# TC2030-NL_TagConnect_6-pin.net
KiCad netlist of a schematic drawn in Altium Designer
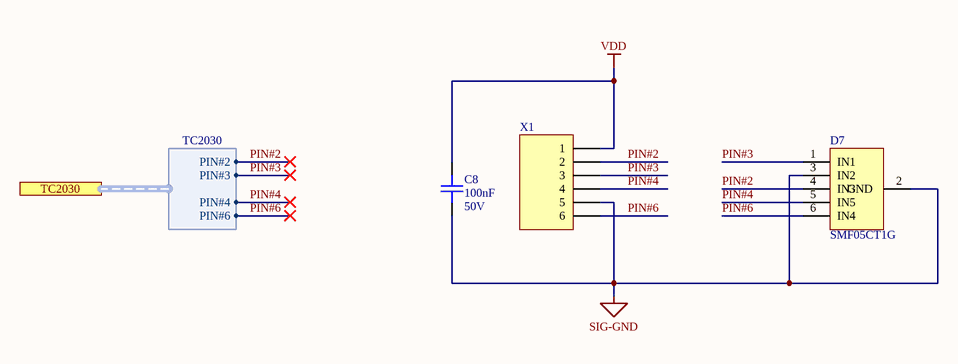
[diagram p0: TC2030-NL_TagConnect_6-pin.SchDoc]

(export (version "E")
  (design (tool "Eeschema 10.0.6"))
  (components
    (comp (ref "C8")
      (value "CAP CER 0.1UF 50V X7R 0402")
      (footprint "C0402")
      (description "0.1µF ±10% 50V Ceramic Capacitor X7R 0402 (1005 Metric)")
      (fields
        (field (name "MANUFACTURER") "TDK")
        (field (name "MANUFACTURER PART NUMBER") "CGA2B3X7R1H104K050BB")
        (field (name "CAPACITANCE") "100nF")
        (field (name "VOLTAGE") "50V")
      )
      (libsource (lib "capacitors_smd") (part "CAP CER 0.1UF 50V X7R 0402"))
    )
    (comp (ref "D7")
      (value "SMF05CT1G")
      (footprint "SOT363_SOP65P210X265-6N")
      (description "12.5V Clamp 8A (8/20µs) Ipp Tvs Diode Surface Mount SC-88/SC70-6/SOT-363")
      (fields (field (name "MANUFACTURER") "ON Semiconductor"))
      (libsource (lib "diodes_tvs") (part "TVS DIODE 5V 12.5V 5CH SC88"))
    )
    (comp (ref "X1")
      (value "~")
      (footprint "TC2030-IDC-NL")
      (description "Tag-Connect TC2030-MCP-NL (3x2 pins No Legs)")
      (fields
        (field (name "MANUFACTURER") "Tag-Connect LLC")
        (field (name "MANUFACTURER PART NUMBER") "TC2030-IDC-NL")
      )
      (libsource (lib "EvansWerks") (part "TC2030-IDC-NL"))
    )
  )
  (nets
    (net (code "2") (name "/PIN#2") (class "Default")
      (node (ref "D7") (pin "4") (pinfunction "IN3_4") (pintype "passive"))
      (node (ref "X1") (pin "2") (pinfunction "2_2") (pintype "passive"))
    )
    (net (code "3") (name "/PIN#3") (class "Default")
      (node (ref "D7") (pin "1") (pinfunction "IN1_1") (pintype "passive"))
      (node (ref "X1") (pin "3") (pinfunction "3_3") (pintype "passive"))
    )
    (net (code "4") (name "/PIN#4") (class "Default")
      (node (ref "D7") (pin "5") (pinfunction "IN5_5") (pintype "passive"))
      (node (ref "X1") (pin "4") (pinfunction "4_4") (pintype "passive"))
    )
    (net (code "5") (name "/PIN#6") (class "Default")
      (node (ref "D7") (pin "6") (pinfunction "IN4_6") (pintype "passive"))
      (node (ref "X1") (pin "6") (pinfunction "6_6") (pintype "passive"))
    )
    (net (code "7") (name "SIG-GND") (class "Default")
      (node (ref "C8") (pin "1") (pinfunction "1_1") (pintype "passive"))
      (node (ref "D7") (pin "2") (pinfunction "GND_2") (pintype "power_in"))
      (node (ref "D7") (pin "3") (pinfunction "IN2_3") (pintype "passive"))
      (node (ref "X1") (pin "5") (pinfunction "5_5") (pintype "passive"))
    )
    (net (code "8") (name "VDD") (class "Default")
      (node (ref "C8") (pin "2") (pinfunction "2_2") (pintype "passive"))
      (node (ref "X1") (pin "1") (pinfunction "1_1") (pintype "passive"))
    )
  )
)
